# ADC_Reference.net
KiCad netlist of a schematic drawn in Altium Designer
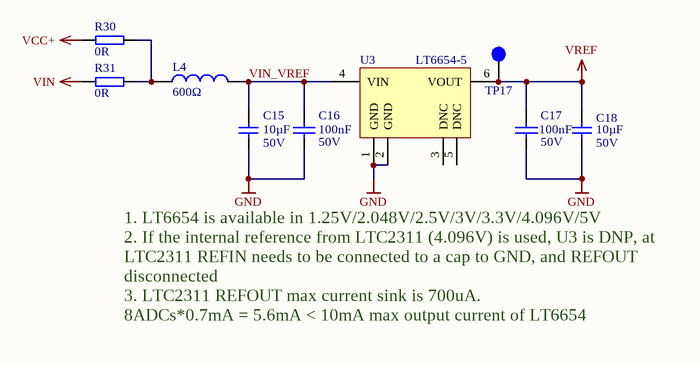
[diagram p0: ADC_Reference.SchDoc]

(export (version "E")
  (design (tool "Eeschema 10.0.6"))
  (components
    (comp (ref "C15")
      (value "10µF")
      (footprint "C_1206")
      (description "Capacitor 1206")
      (fields (field (name "TOLERANCE") "20%") (field (name "MF") "Samsung") (field (name "VOLTAGE") "50V"))
      (libsource (lib "UltraZohm_ADC") (part "C_1206"))
    )
    (comp (ref "C16")
      (value "100nF")
      (footprint "CAPC1608X07N")
      (fields
        (field (name "MF") "Yageo")
        (field (name "MPN") "CC0603KRX7R9BB104")
        (field (name "VOLTAGE") "50V")
      )
      (libsource (lib "UltraZohm_ADC") (part "Cap_0603"))
    )
    (comp (ref "C17")
      (value "100nF")
      (footprint "CAPC1608X07N")
      (fields
        (field (name "MF") "Yageo")
        (field (name "MPN") "CC0603KRX7R9BB104")
        (field (name "VOLTAGE") "50V")
      )
      (libsource (lib "UltraZohm_ADC") (part "Cap_0603"))
    )
    (comp (ref "C18")
      (value "10µF")
      (footprint "C_1206")
      (description "Capacitor 1206")
      (fields
        (field (name "TOLERANCE") "10%")
        (field (name "MF") "Samsung")
        (field (name "VOLTAGE") "50V")
        (field (name "CREATED") "2020_09_17_Liegmann")
      )
      (libsource (lib "UltraZohm_ADC") (part "C_1206"))
    )
    (comp (ref "L4")
      (value "600Ω")
      (footprint "WE-CBF_0805_High Current")
      (description "WE-CBF SMD EMI Suppression Ferrite Bead, 0805, 600Ω")
      (fields (field (name "MF") "Wurth Elektronik") (field (name "MPN") "742792040"))
      (libsource (lib "UltraZohm_ADC") (part "WE-CBF, 742792040"))
    )
    (comp (ref "R30")
      (value "0R")
      (footprint "RESC1608X06N")
      (fields (field (name "MF") "Vishay / Dale") (field (name "MPN") "CRCW06030000Z0EBC"))
      (libsource (lib "UltraZohm_ADC") (part "R_0603"))
    )
    (comp (ref "R31")
      (value "0R")
      (footprint "RESC1608X06N")
      (fields (field (name "MF") "Vishay / Dale") (field (name "MPN") "CRCW06030000Z0EBC"))
      (libsource (lib "UltraZohm_ADC") (part "R_0603"))
    )
    (comp (ref "TP17")
      (value "VREF")
      (footprint "TP_1mm")
      (description "Testpoint 1mm")
      (fields (field (name "CREATED") "2018_06_25_AGeiger"))
      (libsource (lib "UltraZOhm_CarrierBoard") (part "TP_1mm"))
    )
    (comp (ref "U3")
      (value "LT6654-5")
      (footprint "SOT95P280X100-6N")
      (fields (field (name "MF") "Analog Devices") (field (name "MPN") "LT6654AIS6-5#TRMPBF"))
      (libsource (lib "UltraZohm_ADC") (part "LT6654"))
    )
  )
  (nets
    (net (code "1") (name "/VIN_VREF") (class "Default")
      (node (ref "C15") (pin "2") (pinfunction "2_2") (pintype "passive"))
      (node (ref "C16") (pin "1") (pinfunction "1_1") (pintype "passive"))
      (node (ref "L4") (pin "2") (pinfunction "2_2") (pintype "passive"))
      (node (ref "U3") (pin "4") (pinfunction "VIN_4") (pintype "power_in"))
    )
    (net (code "2") (name "GND") (class "Default")
      (node (ref "C15") (pin "1") (pinfunction "1_1") (pintype "passive"))
      (node (ref "C16") (pin "2") (pinfunction "2_2") (pintype "passive"))
      (node (ref "C17") (pin "2") (pinfunction "2_2") (pintype "passive"))
      (node (ref "C18") (pin "1") (pinfunction "1_1") (pintype "passive"))
      (node (ref "U3") (pin "1") (pinfunction "GND_1") (pintype "power_in"))
      (node (ref "U3") (pin "2") (pinfunction "GND_2") (pintype "power_in"))
    )
    (net (code "3") (name "Net-(L4-Pad1)") (class "Default")
      (node (ref "L4") (pin "1") (pinfunction "1_1") (pintype "passive"))
      (node (ref "R30") (pin "2") (pintype "passive"))
      (node (ref "R31") (pin "2") (pintype "passive"))
    )
    (net (code "4") (name "VCC+") (class "Default") (node (ref "R30") (pin "1") (pintype "passive")))
    (net (code "5") (name "VIN") (class "Default") (node (ref "R31") (pin "1") (pintype "passive")))
    (net (code "6") (name "VREF") (class "Default")
      (node (ref "C17") (pin "1") (pinfunction "1_1") (pintype "passive"))
      (node (ref "C18") (pin "2") (pinfunction "2_2") (pintype "passive"))
      (node (ref "TP17") (pin "1") (pintype "passive"))
      (node (ref "U3") (pin "6") (pinfunction "VOUT_6") (pintype "power_in"))
    )
    (net (code "7") (name "unconnected-(U3-DNC-Pad3)") (class "Default")
      (node (ref "U3") (pin "3") (pinfunction "DNC_3") (pintype "passive"))
    )
    (net (code "8") (name "unconnected-(U3-DNC-Pad5)") (class "Default")
      (node (ref "U3") (pin "5") (pinfunction "DNC_5") (pintype "passive"))
    )
  )
)
